# Schematics.net
KiCad netlist of a schematic drawn in Altium Designer
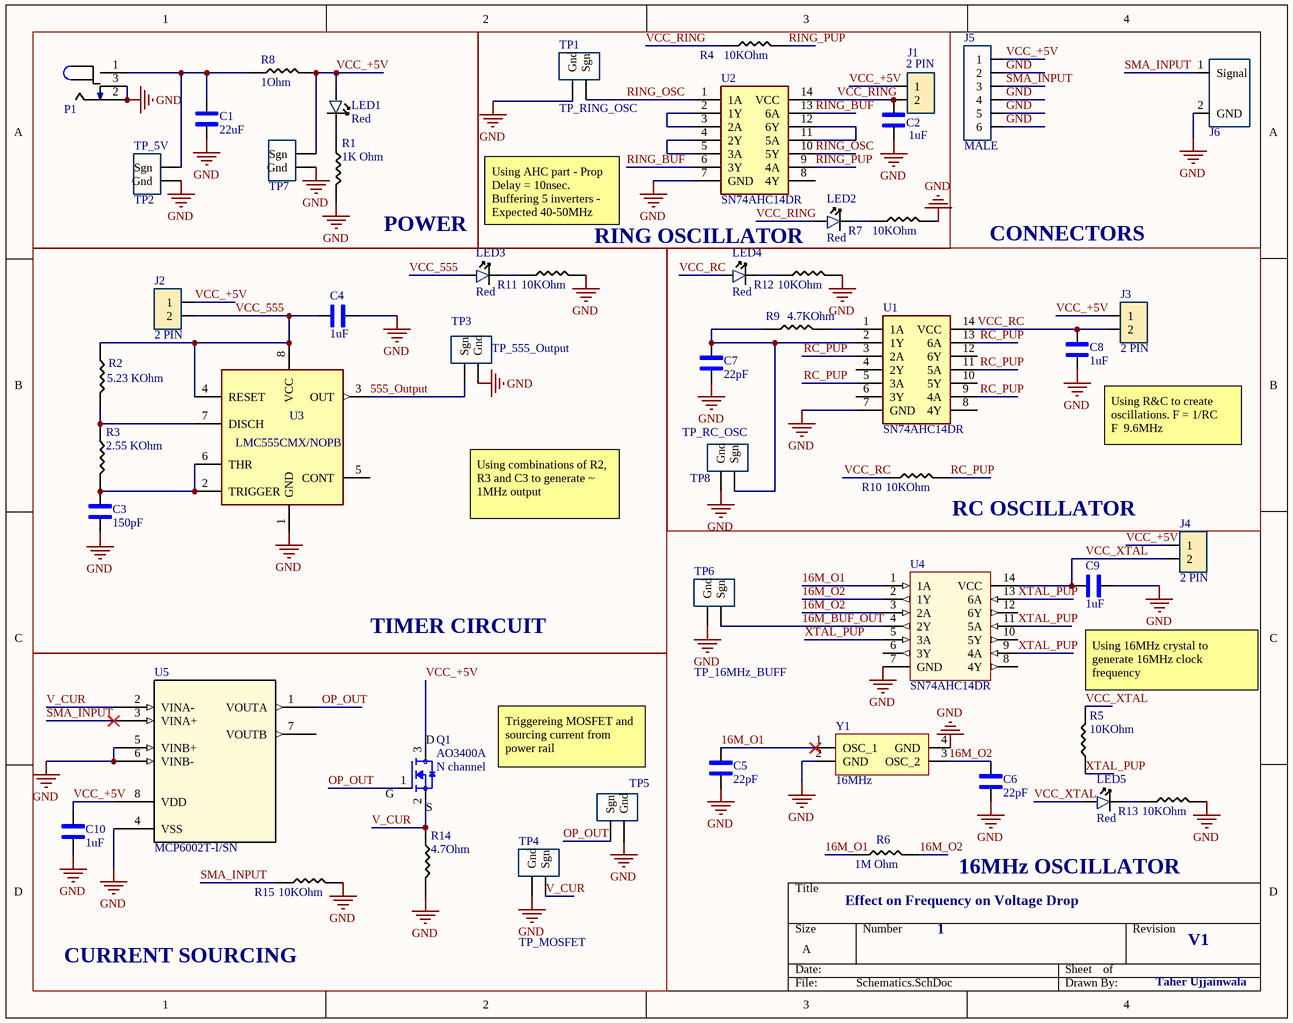
[diagram p0: Schematics.SchDoc]

(export (version "E")
  (design (tool "Eeschema 10.0.6"))
  (components
    (comp (ref "C1")
      (value "22uF")
      (footprint "0805_Passive_Capaciitor")
      (description "MULTILAYER CERAMIC CAPACITORS MLCC - SMD/SMT 22UF 25V 0805 ROHS")
      (fields (field (name "MFR PART #") "CL21A226MAQNNNE") (field (name "LCSC PART#") "C45783"))
      (libsource (lib "ECEN5730Lib_JLC_2021_08") (part "C_22uF_0805"))
    )
    (comp (ref "C2")
      (value "1uF")
      (footprint "0402_Passive_Capacitor")
      (description "MULTILAYER CERAMIC CAPACITORS MLCC - SMD/SMT 1UF 25V 0402 ROHS")
      (fields (field (name "MFR PART #") "CL05A105KA5NQNC") (field (name "LCSC PART#") "C52923"))
      (libsource (lib "ECEN5730Lib_2023_01_DS") (part "C_1uF_0402"))
    )
    (comp (ref "C3")
      (value "150pF")
      (footprint "0402_Passive_Capacitor")
      (description "MULTILAYER CERAMIC CAPACITORS MLCC - SMD/SMT 1UF 25V 0402 ROHS")
      (fields (field (name "MFR PART #") "0402B151K500NT") (field (name "LCSC PART#") "C1527"))
      (libsource (lib "ECEN5730Lib_2023_01_DS") (part "C_150pF_0402"))
    )
    (comp (ref "C4")
      (value "1uF")
      (footprint "0402_Passive_Capacitor")
      (description "MULTILAYER CERAMIC CAPACITORS MLCC - SMD/SMT 1UF 25V 0402 ROHS")
      (fields (field (name "MFR PART #") "CL05A105KA5NQNC") (field (name "LCSC PART#") "C52923"))
      (libsource (lib "ECEN5730Lib_2023_01_DS") (part "C_1uF_0402"))
    )
    (comp (ref "C5")
      (value "22pF")
      (footprint "0402_Passive_Capacitor")
      (description "MULTILAYER CERAMIC CAPACITORS MLCC - SMD/SMT 22PF 50V 0402 ROHS")
      (fields (field (name "MFR PART #") "0402CG220J500NT") (field (name "LCSC PART#") "C1555"))
      (libsource (lib "ECEN5730Lib_2023_01_DS") (part "C_22pF_0402"))
    )
    (comp (ref "C6")
      (value "22pF")
      (footprint "0402_Passive_Capacitor")
      (description "MULTILAYER CERAMIC CAPACITORS MLCC - SMD/SMT 22PF 50V 0402 ROHS")
      (fields (field (name "MFR PART #") "0402CG220J500NT") (field (name "LCSC PART#") "C1555"))
      (libsource (lib "ECEN5730Lib_2023_01_DS") (part "C_22pF_0402"))
    )
    (comp (ref "C7")
      (value "22pF")
      (footprint "0402_Passive_Capacitor")
      (description "MULTILAYER CERAMIC CAPACITORS MLCC - SMD/SMT 22PF 50V 0402 ROHS")
      (fields (field (name "MFR PART #") "0402CG220J500NT") (field (name "LCSC PART#") "C1555"))
      (libsource (lib "ECEN5730Lib_2023_01_DS") (part "C_22pF_0402"))
    )
    (comp (ref "C8")
      (value "1uF")
      (footprint "0402_Passive_Capacitor")
      (description "MULTILAYER CERAMIC CAPACITORS MLCC - SMD/SMT 1UF 25V 0402 ROHS")
      (fields (field (name "MFR PART #") "CL05A105KA5NQNC") (field (name "LCSC PART#") "C52923"))
      (libsource (lib "ECEN5730Lib_2023_01_DS") (part "C_1uF_0402"))
    )
    (comp (ref "C9")
      (value "1uF")
      (footprint "0402_Passive_Capacitor")
      (description "MULTILAYER CERAMIC CAPACITORS MLCC - SMD/SMT 1UF 25V 0402 ROHS")
      (fields (field (name "MFR PART #") "CL05A105KA5NQNC") (field (name "LCSC PART#") "C52923"))
      (libsource (lib "ECEN5730Lib_2023_01_DS") (part "C_1uF_0402"))
    )
    (comp (ref "C10")
      (value "1uF")
      (footprint "0402_Passive_Capacitor")
      (description "MULTILAYER CERAMIC CAPACITORS MLCC - SMD/SMT 1UF 25V 0402 ROHS")
      (fields (field (name "MFR PART #") "CL05A105KA5NQNC") (field (name "LCSC PART#") "C52923"))
      (libsource (lib "ECEN5730Lib_JLC_2021_08") (part "C_1uF_0402"))
    )
    (comp (ref "J1")
      (value "2 PIN")
      (footprint "2_PIN_100MIL")
      (description "2.54mm Straight 2 1 Header，Breakaway Through Hole,P=2.54mm Pin Header & Female Header ROHS")
      (fields (field (name "LCSC PART#") "C124375") (field (name "MFR PART #") "B-2100S02P-A110"))
      (libsource (lib "ECEN5730Lib_2023_01_DS") (part "JM_2_PIN_MALE"))
    )
    (comp (ref "J2")
      (value "2 PIN")
      (footprint "2_PIN_100MIL")
      (description "2.54mm Straight 2 1 Header，Breakaway Through Hole,P=2.54mm Pin Header & Female Header ROHS")
      (fields (field (name "LCSC PART#") "C124375") (field (name "MFR PART #") "B-2100S02P-A110"))
      (libsource (lib "") (part "JM_2_PIN_MALE_1"))
    )
    (comp (ref "J3")
      (value "2 PIN")
      (footprint "2_PIN_100MIL")
      (description "2.54mm Straight 2 1 Header，Breakaway Through Hole,P=2.54mm Pin Header & Female Header ROHS")
      (fields (field (name "LCSC PART#") "C124375") (field (name "MFR PART #") "B-2100S02P-A110"))
      (libsource (lib "ECEN5730Lib_2023_01_DS") (part "JM_2_PIN_MALE"))
    )
    (comp (ref "J4")
      (value "2 PIN")
      (footprint "2_PIN_100MIL")
      (description "2.54mm Straight 2 1 Header，Breakaway Through Hole,P=2.54mm Pin Header & Female Header ROHS")
      (fields (field (name "LCSC PART#") "C124375") (field (name "MFR PART #") "B-2100S02P-A110"))
      (libsource (lib "ECEN5730Lib_2023_01_DS") (part "JM_2_PIN_MALE"))
    )
    (comp (ref "J5")
      (value "MALE")
      (footprint "6_PIN_100MIL-Male")
      (description "Male header- 6 pin 1 row- through Hole")
      (fields (field (name "LCSC PART#") "C37208"))
      (libsource (lib "ECEN5730Lib_2023_01_DS") (part "JM_6_PIN_MALE"))
    )
    (comp (ref "J6")
      (value "SMA Edge Launched")
      (footprint "SMA_2_LAYER")
      (description "2 Layer SMA Connector Without Cutout Under Signal")
      (libsource (lib "ECEN5730Lib_Manual_2021_08") (part "J_SMA_2_Layer"))
    )
    (comp (ref "LED1")
      (value "Red")
      (footprint "LED_0603")
      (description "LIGHT EMITTING DIODES (LED) RED 520~625NM 90~100MCD@20MA TOP VIEW 0603 ROHS")
      (fields (field (name "MFR PART #") "KT-0603R") (field (name "LCSC PART#") "C2286"))
      (libsource (lib "ECEN5730Lib_JLC_2021_08") (part "LED_RED_0603"))
    )
    (comp (ref "LED2")
      (value "Red")
      (footprint "LED_0603")
      (description "LIGHT EMITTING DIODES (LED) RED 520~625NM 90~100MCD@20MA TOP VIEW 0603 ROHS")
      (fields (field (name "MFR PART #") "KT-0603R") (field (name "LCSC PART#") "C2286"))
      (libsource (lib "ECEN5730Lib_JLC_2021_08") (part "LED_RED_0603"))
    )
    (comp (ref "LED3")
      (value "Red")
      (footprint "LED_0603")
      (description "LIGHT EMITTING DIODES (LED) RED 520~625NM 90~100MCD@20MA TOP VIEW 0603 ROHS")
      (fields (field (name "MFR PART #") "KT-0603R") (field (name "LCSC PART#") "C2286"))
      (libsource (lib "ECEN5730Lib_JLC_2021_08") (part "LED_RED_0603"))
    )
    (comp (ref "LED4")
      (value "Red")
      (footprint "LED_0603")
      (description "LIGHT EMITTING DIODES (LED) RED 520~625NM 90~100MCD@20MA TOP VIEW 0603 ROHS")
      (fields (field (name "MFR PART #") "KT-0603R") (field (name "LCSC PART#") "C2286"))
      (libsource (lib "ECEN5730Lib_JLC_2021_08") (part "LED_RED_0603"))
    )
    (comp (ref "LED5")
      (value "Red")
      (footprint "LED_0603")
      (description "LIGHT EMITTING DIODES (LED) RED 520~625NM 90~100MCD@20MA TOP VIEW 0603 ROHS")
      (fields (field (name "MFR PART #") "KT-0603R") (field (name "LCSC PART#") "C2286"))
      (libsource (lib "ECEN5730Lib_JLC_2021_08") (part "LED_RED_0603"))
    )
    (comp (ref "P1")
      (value "Power Jack")
      (footprint "Power_Jack")
      (description "Power Barrel Connector Jack 2.10mm ID (0.083\"), 5.50mm OD (0.217\") Through Hole, Right Angle")
      (fields (field (name "DIGIKEY PART") "CP-102A-ND") (field (name "LCSC PART#") "C136744"))
      (libsource (lib "ECEN5730Lib_JLC_2021_08") (part "P_Power Jack"))
    )
    (comp (ref "Q1")
      (value "AO3400A")
      (footprint "N-MOSFET")
      (description "MOSFET N Trench 30V 5.7A 1.5V @ 250uA 26.5 m? @ 5.7A,10V SOT-23-3L RoHS")
      (fields (field (name "LCSC PART#") "C20917") (field (name "ALTIUM_VALUE") "N channel"))
      (libsource (lib "ECEN5730Lib_2023_01_DS") (part "Q_Nch_MOSFET"))
    )
    (comp (ref "R1")
      (value "1K Ohm")
      (footprint "0805_Passive_Resistor")
      (description "CHIP RESISTOR - SURFACE MOUNT 1KOHMS ±1% 1/8W 0805 ROHS")
      (fields (field (name "LCSC PART#") "C17513") (field (name "MFR PART #") "0805W8F1001T5E"))
      (libsource (lib "ECEN5730Lib_JLC_2021_08") (part "R_1K_0805"))
    )
    (comp (ref "R2")
      (value "5.23 KOhm")
      (footprint "0402_Passive_Resistor")
      (fields
        (field (name "MFR PART #") "0402WGF5231TCE")
        (field (name "LCSC PART#") "C25907")
        (field (name "Comment") "1 Ohm")
      )
      (libsource (lib "ECEN5730Lib_2023_01_DS") (part "R_5.23KOhm_0402"))
    )
    (comp (ref "R3")
      (value "2.55 KOhm")
      (footprint "0402_Passive_Resistor")
      (fields
        (field (name "MFR PART #") "RC0402FR-072K55L")
        (field (name "LCSC PART#") "C185431")
        (field (name "Comment") "2.55 KOhms")
      )
      (libsource (lib "ECEN5730Lib_2023_01_DS") (part "R_2.55 KOhm_0402"))
    )
    (comp (ref "R4")
      (value "10KOhm")
      (footprint "0402_Passive_Resistor")
      (description "CHIP RESISTOR - SURFACE MOUNT 10KOHMS ±1% 1/16W 0402 ROHS")
      (fields (field (name "MFR PART #") "0402WGF1002TCE") (field (name "LCSC PART#") "C25744"))
      (libsource (lib "ECEN5730Lib_2023_01_DS") (part "R_10KOhm_0402"))
    )
    (comp (ref "R5")
      (value "10KOhm")
      (footprint "0402_Passive_Resistor")
      (description "CHIP RESISTOR - SURFACE MOUNT 10KOHMS ±1% 1/16W 0402 ROHS")
      (fields (field (name "MFR PART #") "0402WGF1002TCE") (field (name "LCSC PART#") "C25744"))
      (libsource (lib "ECEN5730Lib_2023_01_DS") (part "R_10KOhm_0402"))
    )
    (comp (ref "R6")
      (value "1M Ohm")
      (footprint "0402_Passive_Resistor")
      (description "CHIP RESISTOR - SURFACE MOUNT 1MOHMS ±1% 1/16W 0402 ROHS")
      (fields (field (name "MFR PART #") "0402WGF1004TCE") (field (name "LCSC PART#") "C26083"))
      (libsource (lib "ECEN5730Lib_2023_01_DS") (part "R_1M_0402"))
    )
    (comp (ref "R7")
      (value "10KOhm")
      (footprint "0402_Passive_Resistor")
      (description "CHIP RESISTOR - SURFACE MOUNT 10KOHMS ±1% 1/16W 0402 ROHS")
      (fields (field (name "MFR PART #") "0402WGF1002TCE") (field (name "LCSC PART#") "C25744"))
      (libsource (lib "ECEN5730Lib_2023_01_DS") (part "R_10KOhm_0402"))
    )
    (comp (ref "R8")
      (value "1Ohm")
      (footprint "1206_Passive_Resitor")
      (description "1Ω ±5% 0.25W ±400ppm/℃ 1206 Chip Resistor - Surface Mount RoHS")
      (fields (field (name "LCSC PART#") "C1409") (field (name "MFR PART #") "1206W4J010JT5E"))
      (libsource (lib "ECEN5730Lib_2023_01_DS") (part "R_1Ohm_1206"))
    )
    (comp (ref "R9")
      (value "4.7KOhm")
      (footprint "1206_Passive_Resitor")
      (description "4.7kΩ ±1% 0.25W ±100ppm/℃ 1206 Chip Resistor - Surface Mount RoHS")
      (fields (field (name "LCSC PART#") "C17936") (field (name "MFR PART #") "1206W4F4701T5E"))
      (libsource (lib "ECEN5730Lib_2023_01_DS") (part "R_4.7k_1206"))
    )
    (comp (ref "R10")
      (value "10KOhm")
      (footprint "0402_Passive_Resistor")
      (description "CHIP RESISTOR - SURFACE MOUNT 10KOHMS ±1% 1/16W 0402 ROHS")
      (fields (field (name "MFR PART #") "0402WGF1002TCE") (field (name "LCSC PART#") "C25744"))
      (libsource (lib "ECEN5730Lib_2023_01_DS") (part "R_10KOhm_0402"))
    )
    (comp (ref "R11")
      (value "10KOhm")
      (footprint "0402_Passive_Resistor")
      (description "CHIP RESISTOR - SURFACE MOUNT 10KOHMS ±1% 1/16W 0402 ROHS")
      (fields (field (name "MFR PART #") "0402WGF1002TCE") (field (name "LCSC PART#") "C25744"))
      (libsource (lib "ECEN5730Lib_2023_01_DS") (part "R_10KOhm_0402"))
    )
    (comp (ref "R12")
      (value "10KOhm")
      (footprint "0402_Passive_Resistor")
      (description "CHIP RESISTOR - SURFACE MOUNT 10KOHMS ±1% 1/16W 0402 ROHS")
      (fields (field (name "MFR PART #") "0402WGF1002TCE") (field (name "LCSC PART#") "C25744"))
      (libsource (lib "ECEN5730Lib_2023_01_DS") (part "R_10KOhm_0402"))
    )
    (comp (ref "R13")
      (value "10KOhm")
      (footprint "0402_Passive_Resistor")
      (description "CHIP RESISTOR - SURFACE MOUNT 10KOHMS ±1% 1/16W 0402 ROHS")
      (fields (field (name "MFR PART #") "0402WGF1002TCE") (field (name "LCSC PART#") "C25744"))
      (libsource (lib "ECEN5730Lib_2023_01_DS") (part "R_10KOhm_0402"))
    )
    (comp (ref "R14")
      (value "4.7Ohm")
      (footprint "1206_Passive_Resitor")
      (description "4.7Ω ±5% 0.25W ±400ppm/℃ 1206 Chip Resistor - Surface Mount RoHS")
      (fields (field (name "MFR PART #") "1206W4F470KT5E") (field (name "LCSC PART#") "C17937"))
      (libsource (lib "ECEN5730Lib_2023_01_DS") (part "R_4.7Ohm_1206"))
    )
    (comp (ref "R15")
      (value "10KOhm")
      (footprint "0402_Passive_Resistor")
      (description "CHIP RESISTOR - SURFACE MOUNT 10KOHMS ±1% 1/16W 0402 ROHS")
      (fields (field (name "MFR PART #") "0402WGF1002TCE") (field (name "LCSC PART#") "C25744"))
      (libsource (lib "ECEN5730Lib_2023_01_DS") (part "R_10KOhm_0402"))
    )
    (comp (ref "TP1")
      (value "TP_RING_OSC")
      (footprint "TP10x_Probe")
      (description "Test Point 300 mil centers")
      (libsource (lib "") (part "TP_10x_Probe_1"))
    )
    (comp (ref "TP2")
      (value "TP_5V")
      (footprint "TP10x_Probe")
      (description "Test Point 300 mil centers")
      (libsource (lib "ECEN5730Lib_Manual_2021_08") (part "TP_10x_Probe"))
    )
    (comp (ref "TP3")
      (value "TP_555_Output")
      (footprint "TP10x_Probe")
      (description "Test Point 300 mil centers")
      (libsource (lib "") (part "TP_10x_Probe_2"))
    )
    (comp (ref "TP4")
      (value "TP_MOSFET")
      (footprint "TP10x_Probe")
      (description "Test Point 300 mil centers")
      (libsource (lib "") (part "TP_10x_Probe_1"))
    )
    (comp (ref "TP5")
      (value "10x Probe TP")
      (footprint "TP10x_Probe")
      (description "Test Point 300 mil centers")
      (libsource (lib "") (part "TP_10x_Probe_1"))
    )
    (comp (ref "TP6")
      (value "TP_16MHz_BUFF")
      (footprint "TP10x_Probe")
      (description "Test Point 300 mil centers")
      (libsource (lib "") (part "TP_10x_Probe_1"))
    )
    (comp (ref "TP7")
      (value "10x Probe TP")
      (footprint "TP10x_Probe")
      (description "Test Point 300 mil centers")
      (libsource (lib "ECEN5730Lib_2023_01_DS") (part "TP_10x_Probe"))
    )
    (comp (ref "TP8")
      (value "TP_RC_OSC")
      (footprint "TP10x_Probe")
      (description "Test Point 300 mil centers")
      (libsource (lib "") (part "TP_10x_Probe_1"))
    )
    (comp (ref "U1")
      (value "SN74AHC14DR")
      (footprint "HEX_74AC14")
      (description "Inverter IC 6 Channel Schmitt Trigger 14-SOIC")
      (fields (field (name "LCSC PART#") "C6942"))
      (libsource (lib "ECEN5730Lib_2023_01_DS") (part "U_74_AHC_Hex"))
    )
    (comp (ref "U2")
      (value "SN74AHC14DR")
      (footprint "HEX_74AC14")
      (description "Inverter IC 6 Channel Schmitt Trigger 14-SOIC")
      (fields (field (name "LCSC PART#") "C6942"))
      (libsource (lib "ECEN5730Lib_2023_01_DS") (part "U_74_AHC_Hex"))
    )
    (comp (ref "U3")
      (value "LMC555CMX/NOPB")
      (footprint "TS555IDTTR")
      (description "555 Type, Timer/Oscillator _Single_ IC 3MHz 8-SO")
      (fields (field (name "LCSC PART#") "C90760"))
      (libsource (lib "ECEN5730Lib_JLC_2021_08") (part "U_555_Fast"))
    )
    (comp (ref "U4")
      (value "SN74AHC14DR")
      (footprint "SOIC127P600X175-14N")
      (description "6-ch, 2-V to 5.5-V inverters with Schmitt-Trigger inputs")
      (fields (field (name "MF") "Texas Instruments"))
      (libsource (lib "Hex_Inverter_Libraray") (part "SN74AHC14DR"))
    )
    (comp (ref "U5")
      (value "MCP6002T-I/SN")
      (footprint "SOIC127P600X175-8N")
      (description "0.6 V/us 2 1MHz 1.8V ~ 6V 100μA General Purpose SOIC-8_150mil  Operational Amplifier ROHS")
      (fields (field (name "MFR") "Microchip") (field (name "LCSC PART#") "C7377"))
      (libsource (lib "ECEN5730Lib_2023_01_DS") (part "U_MCP6002T-I/SN"))
    )
    (comp (ref "Y1")
      (value "16MHz")
      (footprint "Crystal resonator")
      (description "±10ppm 16000000Hz -40℃~85℃ 贴片无源晶振 60Ω 9pF SMD3225-4P Crystals ROHS")
      (fields (field (name "LCSC PART#") "C13738") (field (name "MFR PART #") "X322516MLB4SI"))
      (libsource (lib "ECEN5730Lib_2023_01_DS") (part "X_16Mhz_Res"))
    )
  )
  (nets
    (net (code "1") (name "/16M_BUF_OUT") (class "Default")
      (node (ref "TP6") (pin "1") (pinfunction "Sgn_1") (pintype "passive"))
      (node (ref "U4") (pin "4") (pinfunction "2Y_4") (pintype "output"))
    )
    (net (code "2") (name "/16M_O1") (class "Default")
      (node (ref "C5") (pin "2") (pinfunction "2_2") (pintype "passive"))
      (node (ref "R6") (pin "1") (pinfunction "1_1") (pintype "passive"))
      (node (ref "U4") (pin "1") (pinfunction "1A_1") (pintype "input"))
      (node (ref "Y1") (pin "1") (pinfunction "OSC_1_1") (pintype "passive"))
    )
    (net (code "3") (name "/16M_O2") (class "Default")
      (node (ref "C6") (pin "2") (pinfunction "2_2") (pintype "passive"))
      (node (ref "R6") (pin "2") (pinfunction "2_2") (pintype "passive"))
      (node (ref "U4") (pin "2") (pinfunction "1Y_2") (pintype "output"))
      (node (ref "U4") (pin "3") (pinfunction "2A_3") (pintype "input"))
      (node (ref "Y1") (pin "3") (pinfunction "OSC_2_3") (pintype "passive"))
    )
    (net (code "4") (name "/555_Output") (class "Default")
      (node (ref "TP3") (pin "1") (pinfunction "Sgn_1") (pintype "passive"))
      (node (ref "U3") (pin "3") (pinfunction "OUT_3") (pintype "output"))
    )
    (net (code "5") (name "/OP_OUT") (class "Default")
      (node (ref "Q1") (pin "1") (pinfunction "G_1") (pintype "passive"))
      (node (ref "TP5") (pin "1") (pinfunction "Sgn_1") (pintype "passive"))
      (node (ref "U5") (pin "1") (pinfunction "VOUTA_1") (pintype "output"))
    )
    (net (code "6") (name "/RC_PUP") (class "Default")
      (node (ref "R10") (pin "2") (pinfunction "2_2") (pintype "passive"))
      (node (ref "U1") (pin "11") (pinfunction "5A_11") (pintype "passive"))
      (node (ref "U1") (pin "13") (pinfunction "6A_13") (pintype "passive"))
      (node (ref "U1") (pin "3") (pinfunction "2A_3") (pintype "passive"))
      (node (ref "U1") (pin "5") (pinfunction "3A_5") (pintype "passive"))
      (node (ref "U1") (pin "9") (pinfunction "4A_9") (pintype "passive"))
    )
    (net (code "7") (name "/RING_BUF") (class "Default")
      (node (ref "U2") (pin "13") (pinfunction "6A_13") (pintype "passive"))
      (node (ref "U2") (pin "6") (pinfunction "3Y_6") (pintype "passive"))
    )
    (net (code "8") (name "/RING_OSC") (class "Default")
      (node (ref "TP1") (pin "1") (pinfunction "Sgn_1") (pintype "passive"))
      (node (ref "U2") (pin "1") (pinfunction "1A_1") (pintype "passive"))
      (node (ref "U2") (pin "10") (pinfunction "5Y_10") (pintype "passive"))
    )
    (net (code "9") (name "/RING_PUP") (class "Default")
      (node (ref "R4") (pin "2") (pinfunction "2_2") (pintype "passive"))
      (node (ref "U2") (pin "9") (pinfunction "4A_9") (pintype "passive"))
    )
    (net (code "10") (name "/SMA_INPUT") (class "Default")
      (node (ref "J5") (pin "3") (pinfunction "3_3") (pintype "passive"))
      (node (ref "J6") (pin "1") (pinfunction "Signal_1") (pintype "passive"))
      (node (ref "R15") (pin "1") (pinfunction "1_1") (pintype "passive"))
      (node (ref "U5") (pin "3") (pinfunction "VINA+_3") (pintype "input"))
    )
    (net (code "11") (name "/VCC_+5V") (class "Default")
      (node (ref "C10") (pin "2") (pinfunction "2_2") (pintype "passive"))
      (node (ref "J1") (pin "1") (pinfunction "1_1") (pintype "passive"))
      (node (ref "J2") (pin "1") (pinfunction "1_1") (pintype "passive"))
      (node (ref "J3") (pin "1") (pinfunction "1_1") (pintype "passive"))
      (node (ref "J4") (pin "1") (pinfunction "1_1") (pintype "passive"))
      (node (ref "J5") (pin "1") (pinfunction "1_1") (pintype "passive"))
      (node (ref "LED1") (pin "1") (pinfunction "1_1") (pintype "passive"))
      (node (ref "Q1") (pin "3") (pinfunction "D_3") (pintype "passive"))
      (node (ref "R8") (pin "2") (pinfunction "2_2") (pintype "passive"))
      (node (ref "TP7") (pin "1") (pinfunction "Sgn_1") (pintype "passive"))
      (node (ref "U5") (pin "8") (pinfunction "VDD_8") (pintype "passive"))
    )
    (net (code "12") (name "/VCC_555") (class "Default")
      (node (ref "C4") (pin "1") (pinfunction "1_1") (pintype "passive"))
      (node (ref "J2") (pin "2") (pinfunction "2_2") (pintype "passive"))
      (node (ref "LED3") (pin "1") (pinfunction "1_1") (pintype "passive"))
      (node (ref "R2") (pin "1") (pinfunction "1_1") (pintype "passive"))
      (node (ref "U3") (pin "4") (pinfunction "RESET_4") (pintype "passive"))
      (node (ref "U3") (pin "8") (pinfunction "VCC_8") (pintype "power_in"))
    )
    (net (code "13") (name "/VCC_RC") (class "Default")
      (node (ref "C8") (pin "2") (pinfunction "2_2") (pintype "passive"))
      (node (ref "J3") (pin "2") (pinfunction "2_2") (pintype "passive"))
      (node (ref "LED4") (pin "1") (pinfunction "1_1") (pintype "passive"))
      (node (ref "R10") (pin "1") (pinfunction "1_1") (pintype "passive"))
      (node (ref "U1") (pin "14") (pinfunction "VCC_14") (pintype "passive"))
    )
    (net (code "14") (name "/VCC_RING") (class "Default")
      (node (ref "C2") (pin "2") (pinfunction "2_2") (pintype "passive"))
      (node (ref "J1") (pin "2") (pinfunction "2_2") (pintype "passive"))
      (node (ref "LED2") (pin "1") (pinfunction "1_1") (pintype "passive"))
      (node (ref "R4") (pin "1") (pinfunction "1_1") (pintype "passive"))
      (node (ref "U2") (pin "14") (pinfunction "VCC_14") (pintype "passive"))
    )
    (net (code "15") (name "/VCC_XTAL") (class "Default")
      (node (ref "C9") (pin "1") (pinfunction "1_1") (pintype "passive"))
      (node (ref "J4") (pin "2") (pinfunction "2_2") (pintype "passive"))
      (node (ref "LED5") (pin "1") (pinfunction "1_1") (pintype "passive"))
      (node (ref "R5") (pin "2") (pinfunction "2_2") (pintype "passive"))
      (node (ref "U4") (pin "14") (pinfunction "VCC_14") (pintype "power_in"))
    )
    (net (code "16") (name "/V_CUR") (class "Default")
      (node (ref "Q1") (pin "2") (pinfunction "S_2") (pintype "passive"))
      (node (ref "R14") (pin "1") (pinfunction "1_1") (pintype "passive"))
      (node (ref "TP4") (pin "1") (pinfunction "Sgn_1") (pintype "passive"))
      (node (ref "U5") (pin "2") (pinfunction "VINA-_2") (pintype "input"))
    )
    (net (code "17") (name "/XTAL_PUP") (class "Default")
      (node (ref "R5") (pin "1") (pinfunction "1_1") (pintype "passive"))
      (node (ref "U4") (pin "11") (pinfunction "5A_11") (pintype "input"))
      (node (ref "U4") (pin "13") (pinfunction "6A_13") (pintype "input"))
      (node (ref "U4") (pin "5") (pinfunction "3A_5") (pintype "input"))
      (node (ref "U4") (pin "9") (pinfunction "4A_9") (pintype "input"))
    )
    (net (code "18") (name "GND") (class "Default")
      (node (ref "C1") (pin "1") (pinfunction "1_1") (pintype "passive"))
      (node (ref "C10") (pin "1") (pinfunction "1_1") (pintype "passive"))
      (node (ref "C2") (pin "1") (pinfunction "1_1") (pintype "passive"))
      (node (ref "C3") (pin "1") (pinfunction "1_1") (pintype "passive"))
      (node (ref "C4") (pin "2") (pinfunction "2_2") (pintype "passive"))
      (node (ref "C5") (pin "1") (pinfunction "1_1") (pintype "passive"))
      (node (ref "C6") (pin "1") (pinfunction "1_1") (pintype "passive"))
      (node (ref "C7") (pin "1") (pinfunction "1_1") (pintype "passive"))
      (node (ref "C8") (pin "1") (pinfunction "1_1") (pintype "passive"))
      (node (ref "C9") (pin "2") (pinfunction "2_2") (pintype "passive"))
      (node (ref "J5") (pin "2") (pinfunction "2_2") (pintype "passive"))
      (node (ref "J5") (pin "4") (pinfunction "4_4") (pintype "passive"))
      (node (ref "J5") (pin "5") (pinfunction "5_5") (pintype "passive"))
      (node (ref "J5") (pin "6") (pinfunction "6_6") (pintype "passive"))
      (node (ref "J6") (pin "2") (pinfunction "GND_2") (pintype "passive"))
      (node (ref "P1") (pin "2") (pinfunction "2_2") (pintype "power_in"))
      (node (ref "P1") (pin "3") (pinfunction "3_3") (pintype "power_in"))
      (node (ref "R1") (pin "2") (pinfunction "2_2") (pintype "passive"))
      (node (ref "R11") (pin "2") (pinfunction "2_2") (pintype "passive"))
      (node (ref "R12") (pin "2") (pinfunction "2_2") (pintype "passive"))
      (node (ref "R13") (pin "2") (pinfunction "2_2") (pintype "passive"))
      (node (ref "R14") (pin "2") (pinfunction "2_2") (pintype "passive"))
      (node (ref "R15") (pin "2") (pinfunction "2_2") (pintype "passive"))
      (node (ref "R7") (pin "2") (pinfunction "2_2") (pintype "passive"))
      (node (ref "TP1") (pin "2") (pinfunction "Gnd_2") (pintype "passive"))
      (node (ref "TP2") (pin "2") (pinfunction "Gnd_2") (pintype "passive"))
      (node (ref "TP3") (pin "2") (pinfunction "Gnd_2") (pintype "passive"))
      (node (ref "TP4") (pin "2") (pinfunction "Gnd_2") (pintype "passive"))
      (node (ref "TP5") (pin "2") (pinfunction "Gnd_2") (pintype "passive"))
      (node (ref "TP6") (pin "2") (pinfunction "Gnd_2") (pintype "passive"))
      (node (ref "TP7") (pin "2") (pinfunction "Gnd_2") (pintype "passive"))
      (node (ref "TP8") (pin "2") (pinfunction "Gnd_2") (pintype "passive"))
      (node (ref "U1") (pin "7") (pinfunction "GND_7") (pintype "passive"))
      (node (ref "U2") (pin "7") (pinfunction "GND_7") (pintype "passive"))
      (node (ref "U3") (pin "1") (pinfunction "GND_1") (pintype "power_in"))
      (node (ref "U4") (pin "7") (pinfunction "GND_7") (pintype "power_in"))
      (node (ref "U5") (pin "4") (pinfunction "VSS_4") (pintype "passive"))
      (node (ref "U5") (pin "5") (pinfunction "VINB+_5") (pintype "input"))
      (node (ref "U5") (pin "6") (pinfunction "VINB-_6") (pintype "input"))
      (node (ref "Y1") (pin "2") (pinfunction "GND_2") (pintype "passive"))
      (node (ref "Y1") (pin "4") (pinfunction "GND_4") (pintype "passive"))
    )
    (net (code "19") (name "Net-(LED1-Pad2)") (class "Default")
      (node (ref "LED1") (pin "2") (pinfunction "2_2") (pintype "passive"))
      (node (ref "R1") (pin "1") (pinfunction "1_1") (pintype "passive"))
    )
    (net (code "20") (name "Net-(LED2-Pad2)") (class "Default")
      (node (ref "LED2") (pin "2") (pinfunction "2_2") (pintype "passive"))
      (node (ref "R7") (pin "1") (pinfunction "1_1") (pintype "passive"))
    )
    (net (code "21") (name "Net-(LED3-Pad2)") (class "Default")
      (node (ref "LED3") (pin "2") (pinfunction "2_2") (pintype "passive"))
      (node (ref "R11") (pin "1") (pinfunction "1_1") (pintype "passive"))
    )
    (net (code "22") (name "Net-(LED4-Pad2)") (class "Default")
      (node (ref "LED4") (pin "2") (pinfunction "2_2") (pintype "passive"))
      (node (ref "R12") (pin "1") (pinfunction "1_1") (pintype "passive"))
    )
    (net (code "23") (name "Net-(LED5-Pad2)") (class "Default")
      (node (ref "LED5") (pin "2") (pinfunction "2_2") (pintype "passive"))
      (node (ref "R13") (pin "1") (pinfunction "1_1") (pintype "passive"))
    )
    (net (code "24") (name "Net-(TP2-Sgn)") (class "Default")
      (node (ref "C1") (pin "2") (pinfunction "2_2") (pintype "passive"))
      (node (ref "P1") (pin "1") (pinfunction "1_1") (pintype "power_in"))
      (node (ref "R8") (pin "1") (pinfunction "1_1") (pintype "passive"))
      (node (ref "TP2") (pin "1") (pinfunction "Sgn_1") (pintype "passive"))
    )
    (net (code "25") (name "Net-(TP8-Sgn)") (class "Default")
      (node (ref "C7") (pin "2") (pinfunction "2_2") (pintype "passive"))
      (node (ref "R9") (pin "1") (pinfunction "1_1") (pintype "passive"))
      (node (ref "TP8") (pin "1") (pinfunction "Sgn_1") (pintype "passive"))
      (node (ref "U1") (pin "2") (pinfunction "1Y_2") (pintype "passive"))
    )
    (net (code "26") (name "Net-(U1-1A)") (class "Default")
      (node (ref "R9") (pin "2") (pinfunction "2_2") (pintype "passive"))
      (node (ref "U1") (pin "1") (pinfunction "1A_1") (pintype "passive"))
    )
    (net (code "27") (name "Net-(U2-1Y)") (class "Default")
      (node (ref "U2") (pin "2") (pinfunction "1Y_2") (pintype "passive"))
      (node (ref "U2") (pin "3") (pinfunction "2A_3") (pintype "passive"))
    )
    (net (code "28") (name "Net-(U2-2Y)") (class "Default")
      (node (ref "U2") (pin "4") (pinfunction "2Y_4") (pintype "passive"))
      (node (ref "U2") (pin "5") (pinfunction "3A_5") (pintype "passive"))
    )
    (net (code "29") (name "Net-(U2-5A)") (class "Default")
      (node (ref "U2") (pin "11") (pinfunction "5A_11") (pintype "passive"))
      (node (ref "U2") (pin "12") (pinfunction "6Y_12") (pintype "passive"))
    )
    (net (code "30") (name "Net-(U3-DISCH)") (class "Default")
      (node (ref "R2") (pin "2") (pinfunction "2_2") (pintype "passive"))
      (node (ref "R3") (pin "1") (pinfunction "1_1") (pintype "passive"))
      (node (ref "U3") (pin "7") (pinfunction "DISCH_7") (pintype "passive"))
    )
    (net (code "31") (name "Net-(U3-THR)") (class "Default")
      (node (ref "C3") (pin "2") (pinfunction "2_2") (pintype "passive"))
      (node (ref "R3") (pin "2") (pinfunction "2_2") (pintype "passive"))
      (node (ref "U3") (pin "2") (pinfunction "TRIGGER_2") (pintype "passive"))
      (node (ref "U3") (pin "6") (pinfunction "THR_6") (pintype "passive"))
    )
    (net (code "32") (name "unconnected-(U1-2Y-Pad4)") (class "Default")
      (node (ref "U1") (pin "4") (pinfunction "2Y_4") (pintype "passive"))
    )
    (net (code "33") (name "unconnected-(U1-3Y-Pad6)") (class "Default")
      (node (ref "U1") (pin "6") (pinfunction "3Y_6") (pintype "passive"))
    )
    (net (code "34") (name "unconnected-(U1-4Y-Pad8)") (class "Default")
      (node (ref "U1") (pin "8") (pinfunction "4Y_8") (pintype "passive"))
    )
    (net (code "35") (name "unconnected-(U1-5Y-Pad10)") (class "Default")
      (node (ref "U1") (pin "10") (pinfunction "5Y_10") (pintype "passive"))
    )
    (net (code "36") (name "unconnected-(U1-6Y-Pad12)") (class "Default")
      (node (ref "U1") (pin "12") (pinfunction "6Y_12") (pintype "passive"))
    )
    (net (code "37") (name "unconnected-(U2-4Y-Pad8)") (class "Default")
      (node (ref "U2") (pin "8") (pinfunction "4Y_8") (pintype "passive"))
    )
    (net (code "38") (name "unconnected-(U3-CONT-Pad5)") (class "Default")
      (node (ref "U3") (pin "5") (pinfunction "CONT_5") (pintype "passive"))
    )
    (net (code "39") (name "unconnected-(U4-3Y-Pad6)") (class "Default")
      (node (ref "U4") (pin "6") (pinfunction "3Y_6") (pintype "output"))
    )
    (net (code "40") (name "unconnected-(U4-4Y-Pad8)") (class "Default")
      (node (ref "U4") (pin "8") (pinfunction "4Y_8") (pintype "output"))
    )
    (net (code "41") (name "unconnected-(U4-5Y-Pad10)") (class "Default")
      (node (ref "U4") (pin "10") (pinfunction "5Y_10") (pintype "output"))
    )
    (net (code "42") (name "unconnected-(U4-6Y-Pad12)") (class "Default")
      (node (ref "U4") (pin "12") (pinfunction "6Y_12") (pintype "output"))
    )
    (net (code "43") (name "unconnected-(U5-VOUTB-Pad7)") (class "Default")
      (node (ref "U5") (pin "7") (pinfunction "VOUTB_7") (pintype "output"))
    )
  )
)
